# Clock_Distribution.net
KiCad netlist of a schematic drawn in Altium Designer
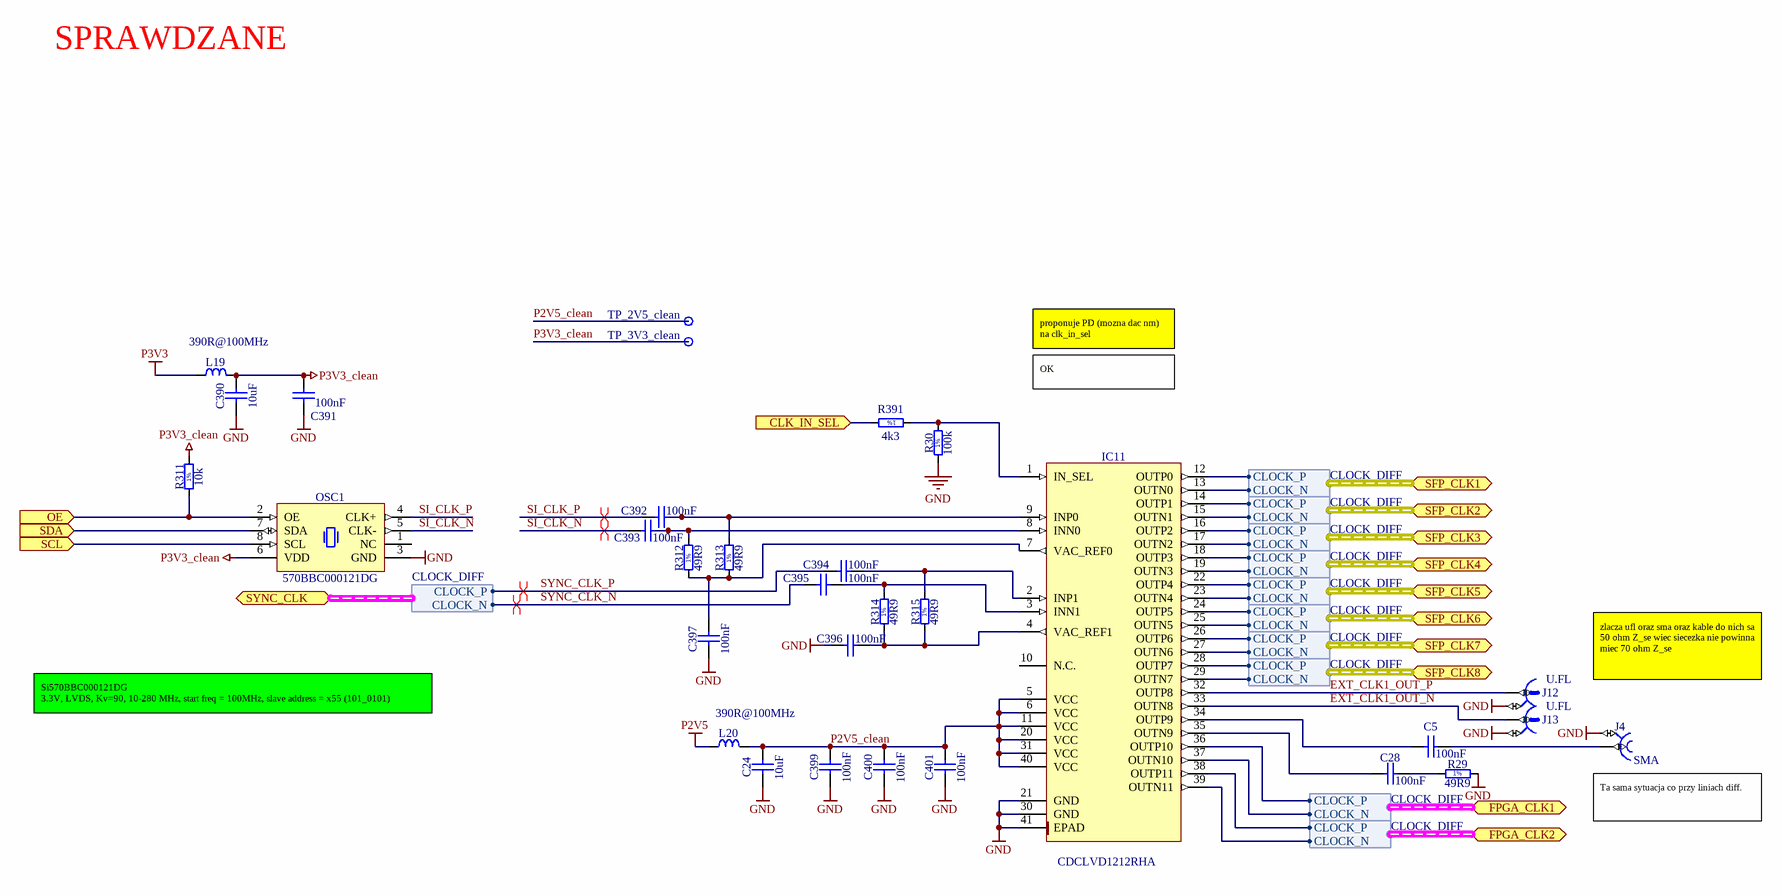
[diagram p0: Clock_Distribution.SchDoc]

(export (version "E")
  (design (tool "Eeschema 10.0.6"))
  (components
    (comp (ref "C5")
      (value "100nF")
      (footprint "CAPC1005X55N")
      (description "Non-polarised capacitor")
      (fields
        (field (name "PART NUMBER") "CC0402_100NF_16V_10%_X7R")
        (field (name "VOLTAGE") "16V")
        (field (name "AUTHOR") "CERN DEM JLC")
      )
      (libsource (lib "Capacitors") (part "Capacitor - non polarized"))
    )
    (comp (ref "C24")
      (value "10uF")
      (footprint "CAPC2012X135N")
      (description "Non-polarised capacitor")
      (fields
        (field (name "PART NUMBER") "CC0805_10UF_10V_10%_X7R")
        (field (name "VOLTAGE") "10V")
        (field (name "AUTHOR") "CERN DEM JLC")
      )
      (libsource (lib "Capacitors") (part "Capacitor - non polarized"))
    )
    (comp (ref "C28")
      (value "100nF")
      (footprint "CAPC1005X55N")
      (description "Non-polarised capacitor")
      (fields
        (field (name "PART NUMBER") "CC0402_100NF_16V_10%_X7R")
        (field (name "VOLTAGE") "16V")
        (field (name "AUTHOR") "CERN DEM JLC")
      )
      (libsource (lib "Capacitors") (part "Capacitor - non polarized"))
    )
    (comp (ref "C390")
      (value "10uF")
      (footprint "CAPC2012X135N")
      (description "Non-polarised capacitor")
      (fields
        (field (name "PART NUMBER") "CC0805_10UF_10V_10%_X7R")
        (field (name "VOLTAGE") "10V")
        (field (name "AUTHOR") "CERN DEM JLC")
      )
      (libsource (lib "Capacitors") (part "Capacitor - non polarized"))
    )
    (comp (ref "C391")
      (value "100nF")
      (footprint "CAPC0603X33N")
      (description "Non-polarised capacitor")
      (fields
        (field (name "PART NUMBER") "CC0201_100NF_6.3V_10%_X5R")
        (field (name "VOLTAGE") "6.3V")
        (field (name "AUTHOR") "CERN DEM JLC")
      )
      (libsource (lib "Capacitors") (part "Capacitor - non polarized"))
    )
    (comp (ref "C392")
      (value "100nF")
      (footprint "CAPC0603X33N")
      (description "Non-polarised capacitor")
      (fields
        (field (name "PART NUMBER") "CC0201_100NF_6.3V_10%_X5R")
        (field (name "VOLTAGE") "6.3V")
        (field (name "AUTHOR") "CERN DEM JLC")
      )
      (libsource (lib "Capacitors") (part "Capacitor - non polarized"))
    )
    (comp (ref "C393")
      (value "100nF")
      (footprint "CAPC0603X33N")
      (description "Non-polarised capacitor")
      (fields
        (field (name "PART NUMBER") "CC0201_100NF_6.3V_10%_X5R")
        (field (name "VOLTAGE") "6.3V")
        (field (name "AUTHOR") "CERN DEM JLC")
      )
      (libsource (lib "Capacitors") (part "Capacitor - non polarized"))
    )
    (comp (ref "C394")
      (value "100nF")
      (footprint "CAPC0603X33N")
      (description "Non-polarised capacitor")
      (fields
        (field (name "PART NUMBER") "CC0201_100NF_6.3V_10%_X5R")
        (field (name "VOLTAGE") "6.3V")
        (field (name "AUTHOR") "CERN DEM JLC")
      )
      (libsource (lib "Capacitors") (part "Capacitor - non polarized"))
    )
    (comp (ref "C395")
      (value "100nF")
      (footprint "CAPC0603X33N")
      (description "Non-polarised capacitor")
      (fields
        (field (name "PART NUMBER") "CC0201_100NF_6.3V_10%_X5R")
        (field (name "VOLTAGE") "6.3V")
        (field (name "AUTHOR") "CERN DEM JLC")
      )
      (libsource (lib "Capacitors") (part "Capacitor - non polarized"))
    )
    (comp (ref "C396")
      (value "100nF")
      (footprint "CAPC0603X33N")
      (description "Non-polarised capacitor")
      (fields
        (field (name "PART NUMBER") "CC0201_100NF_6.3V_10%_X5R")
        (field (name "VOLTAGE") "6.3V")
        (field (name "AUTHOR") "CERN DEM JLC")
      )
      (libsource (lib "Capacitors") (part "Capacitor - non polarized"))
    )
    (comp (ref "C397")
      (value "100nF")
      (footprint "CAPC0603X33N")
      (description "Non-polarised capacitor")
      (fields
        (field (name "PART NUMBER") "CC0201_100NF_6.3V_10%_X5R")
        (field (name "VOLTAGE") "6.3V")
        (field (name "AUTHOR") "CERN DEM JLC")
      )
      (libsource (lib "Capacitors") (part "Capacitor - non polarized"))
    )
    (comp (ref "C399")
      (value "100nF")
      (footprint "CAPC0603X33N")
      (description "Non-polarised capacitor")
      (fields
        (field (name "PART NUMBER") "CC0201_100NF_6.3V_10%_X5R")
        (field (name "VOLTAGE") "6.3V")
        (field (name "AUTHOR") "CERN DEM JLC")
      )
      (libsource (lib "Capacitors") (part "Capacitor - non polarized"))
    )
    (comp (ref "C400")
      (value "100nF")
      (footprint "CAPC0603X33N")
      (description "Non-polarised capacitor")
      (fields
        (field (name "PART NUMBER") "CC0201_100NF_6.3V_10%_X5R")
        (field (name "VOLTAGE") "6.3V")
        (field (name "AUTHOR") "CERN DEM JLC")
      )
      (libsource (lib "Capacitors") (part "Capacitor - non polarized"))
    )
    (comp (ref "C401")
      (value "100nF")
      (footprint "CAPC0603X33N")
      (description "Non-polarised capacitor")
      (fields
        (field (name "PART NUMBER") "CC0201_100NF_6.3V_10%_X5R")
        (field (name "VOLTAGE") "6.3V")
        (field (name "AUTHOR") "CERN DEM JLC")
      )
      (libsource (lib "Capacitors") (part "Capacitor - non polarized"))
    )
    (comp (ref "IC11")
      (value "CDCLVD1212RHA")
      (footprint "QFN50P600X600X80-41N-S425")
      (description "2:16 Low Additive Jitter LVDS Buffer")
      (fields (field (name "MANUFACTURER") "TEXAS INSTRUMENTS") (field (name "AUTHOR") "LNLS DIG LOS"))
      (libsource (lib "ICs And Semiconductors") (part "CDCLVD1212"))
    )
    (comp (ref "J4")
      (value "SMA")
      (footprint "HUBER-SUHNER_85_SMA-50-0-101/111_NE")
      (fields
        (field (name "PART NUMBER") "HUBER-SUHNER_85_SMA-50-0-101/111_NE")
        (field (name "MANUFACTURER") "HUBER+SUHNER")
        (field (name "MANUFACTURER PART NUMBER") "85_SMA-50-0-101/111_NE")
        (field (name "AUTHOR") "CERN DEM JLC")
      )
      (libsource (lib "Connectors") (part "Coax_1Female_1Shield"))
    )
    (comp (ref "J12")
      (value "U.FL")
      (footprint "HIROSE_U.FL-R-SMT-1(10)")
      (fields
        (field (name "PART NUMBER") "HIROSE_U.FL-R-SMT-1(10)")
        (field (name "MANUFACTURER") "HIROSE (HRS)")
        (field (name "MANUFACTURER PART NUMBER") "U.FL-R-SMT-1(10)")
        (field (name "AUTHOR") "CERN DEM JLC")
      )
      (libsource (lib "Connectors") (part "Coax_1Male_1Shield"))
    )
    (comp (ref "J13")
      (value "U.FL")
      (footprint "HIROSE_U.FL-R-SMT-1(10)")
      (fields
        (field (name "PART NUMBER") "HIROSE_U.FL-R-SMT-1(10)")
        (field (name "MANUFACTURER") "HIROSE (HRS)")
        (field (name "MANUFACTURER PART NUMBER") "U.FL-R-SMT-1(10)")
        (field (name "AUTHOR") "CERN DEM JLC")
      )
      (libsource (lib "Connectors") (part "Coax_1Male_1Shield"))
    )
    (comp (ref "L19")
      (value "390R@100MHz")
      (footprint "INDC1608X95N")
      (description "Inductor")
      (fields
        (field (name "PART NUMBER") "IND0603_TDK_MPZ1608R391A")
        (field (name "POWER") "1.2A")
        (field (name "AUTHOR") "CERN DEM JLC")
      )
      (libsource (lib "Inductors & Transformers") (part "Inductor"))
    )
    (comp (ref "L20")
      (value "390R@100MHz")
      (footprint "INDC1608X95N")
      (description "Inductor")
      (fields
        (field (name "PART NUMBER") "IND0603_TDK_MPZ1608R391A")
        (field (name "POWER") "1.2A")
        (field (name "AUTHOR") "CERN DEM JLC")
      )
      (libsource (lib "Inductors & Transformers") (part "Inductor"))
    )
    (comp (ref "OSC1")
      (value "570BBC000121DG")
      (footprint "OSC_SILICON-LAB_SI570")
      (description "Any-Rate I2C Programmable XO Oscillator Si570 Serie")
      (fields
        (field (name "PART NUMBER") "OSC_10-280MHZ_SILICON-LAB_Si570BBC000121DG")
        (field (name "MANUFACTURER") "SILICON LABS")
        (field (name "AUTHOR") "CERN DEM JLC")
      )
      (libsource (lib "ICs And Semiconductors") (part "Oscillator SILICON-LAB_Si570"))
    )
    (comp (ref "R29")
      (value "49R9")
      (footprint "RESC1005X40N")
      (description "Resistor - 1%")
      (fields
        (field (name "PART NUMBER") "R0402_49R9_1%_0.0625W_100PPM")
        (field (name "POWER") "0.0625W")
        (field (name "AUTHOR") "CERN DEM JLC")
      )
      (libsource (lib "Resistors") (part "Resistor - 1%"))
    )
    (comp (ref "R30")
      (value "100k")
      (footprint "RESC1608X55N")
      (description "Resistor - 1%")
      (fields
        (field (name "PART NUMBER") "R0603_100K_1%_0.1W_100PPM")
        (field (name "POWER") "0.1W")
        (field (name "AUTHOR") "CERN DEM JLC")
      )
      (libsource (lib "Resistors") (part "Resistor - 1%"))
    )
    (comp (ref "R311")
      (value "10k")
      (footprint "RESC1005X40N")
      (description "Resistor - 1%")
      (fields
        (field (name "PART NUMBER") "R0402_10K_1%_0.0625W_100PPM")
        (field (name "POWER") "0.0625W")
        (field (name "AUTHOR") "CERN DEM JLC")
      )
      (libsource (lib "Resistors") (part "Resistor - 1%"))
    )
    (comp (ref "R312")
      (value "49R9")
      (footprint "RESC1005X40N")
      (description "Resistor - 1%")
      (fields
        (field (name "PART NUMBER") "R0402_49R9_1%_0.0625W_100PPM")
        (field (name "POWER") "0.0625W")
        (field (name "AUTHOR") "CERN DEM JLC")
      )
      (libsource (lib "Resistors") (part "Resistor - 1%"))
    )
    (comp (ref "R313")
      (value "49R9")
      (footprint "RESC1005X40N")
      (description "Resistor - 1%")
      (fields
        (field (name "PART NUMBER") "R0402_49R9_1%_0.0625W_100PPM")
        (field (name "POWER") "0.0625W")
        (field (name "AUTHOR") "CERN DEM JLC")
      )
      (libsource (lib "Resistors") (part "Resistor - 1%"))
    )
    (comp (ref "R314")
      (value "49R9")
      (footprint "RESC1005X40N")
      (description "Resistor - 1%")
      (fields
        (field (name "PART NUMBER") "R0402_49R9_1%_0.0625W_100PPM")
        (field (name "POWER") "0.0625W")
        (field (name "AUTHOR") "CERN DEM JLC")
      )
      (libsource (lib "Resistors") (part "Resistor - 1%"))
    )
    (comp (ref "R315")
      (value "49R9")
      (footprint "RESC1005X40N")
      (description "Resistor - 1%")
      (fields
        (field (name "PART NUMBER") "R0402_49R9_1%_0.0625W_100PPM")
        (field (name "POWER") "0.0625W")
        (field (name "AUTHOR") "CERN DEM JLC")
      )
      (libsource (lib "Resistors") (part "Resistor - 1%"))
    )
    (comp (ref "R391")
      (value "4k3")
      (footprint "RESC1608X55N")
      (description "Resistor - 1%")
      (fields
        (field (name "PART NUMBER") "R0603_4K3_1%_0.1W_100PPM")
        (field (name "POWER") "0.1W")
        (field (name "AUTHOR") "CERN DEM JLC")
      )
      (libsource (lib "Resistors") (part "Resistor - 1%"))
    )
    (comp (ref "TP_2V5_clean")
      (value "Test Point")
      (footprint "TPS127")
      (fields (field (name "PART NUMBER") "SMD_PAD_1.27X1.27MM") (field (name "AUTHOR") "CERN DEM JLC"))
      (libsource (lib "Eletro-mechanical") (part "Test Point"))
    )
    (comp (ref "TP_3V3_clean")
      (value "Test Point")
      (footprint "TPS127")
      (fields (field (name "PART NUMBER") "SMD_PAD_1.27X1.27MM") (field (name "AUTHOR") "CERN DEM JLC"))
      (libsource (lib "Eletro-mechanical") (part "Test Point"))
    )
  )
  (nets
    (net (code "3") (name "/CLK_IN_SEL") (class "Default")
      (node (ref "R391") (pin "2") (pinfunction "2_2") (pintype "passive"))
    )
    (net (code "4") (name "/EXT_CLK1_OUT_N") (class "Default")
      (node (ref "IC11") (pin "33") (pinfunction "OUTN8_33") (pintype "output"))
      (node (ref "J13") (pin "1") (pinfunction "1_1") (pintype "bidirectional"))
    )
    (net (code "5") (name "/EXT_CLK1_OUT_P") (class "Default")
      (node (ref "IC11") (pin "32") (pinfunction "OUTP8_32") (pintype "output"))
      (node (ref "J12") (pin "1") (pinfunction "1_1") (pintype "bidirectional"))
    )
    (net (code "6") (name "/OE") (class "Default")
      (node (ref "OSC1") (pin "2") (pinfunction "OE_2") (pintype "input"))
      (node (ref "R311") (pin "1") (pinfunction "1_1") (pintype "passive"))
    )
    (net (code "7") (name "/P2V5_clean") (class "Default")
      (node (ref "C24") (pin "2") (pinfunction "2_2") (pintype "passive"))
      (node (ref "C399") (pin "2") (pinfunction "2_2") (pintype "passive"))
      (node (ref "C400") (pin "2") (pinfunction "2_2") (pintype "passive"))
      (node (ref "C401") (pin "2") (pinfunction "2_2") (pintype "passive"))
      (node (ref "IC11") (pin "11") (pinfunction "VCC_11") (pintype "power_in"))
      (node (ref "IC11") (pin "20") (pinfunction "VCC_20") (pintype "power_in"))
      (node (ref "IC11") (pin "31") (pinfunction "VCC_31") (pintype "power_in"))
      (node (ref "IC11") (pin "40") (pinfunction "VCC_40") (pintype "power_in"))
      (node (ref "IC11") (pin "5") (pinfunction "VCC_5") (pintype "power_in"))
      (node (ref "IC11") (pin "6") (pinfunction "VCC_6") (pintype "power_in"))
      (node (ref "L20") (pin "2") (pinfunction "2_2") (pintype "passive"))
      (node (ref "TP_2V5_clean") (pin "1") (pinfunction "1_1") (pintype "bidirectional"))
    )
    (net (code "8") (name "/SCL") (class "Default")
      (node (ref "OSC1") (pin "8") (pinfunction "SCL_8") (pintype "input"))
    )
    (net (code "9") (name "/SDA") (class "Default")
      (node (ref "OSC1") (pin "7") (pinfunction "SDA_7") (pintype "bidirectional"))
    )
    (net (code "11") (name "/SI_CLK_N") (class "Default")
      (node (ref "C393") (pin "2") (pinfunction "2_2") (pintype "passive"))
      (node (ref "OSC1") (pin "5") (pinfunction "CLK-_5") (pintype "output"))
    )
    (net (code "12") (name "/SI_CLK_P") (class "Default")
      (node (ref "C392") (pin "2") (pinfunction "2_2") (pintype "passive"))
      (node (ref "OSC1") (pin "4") (pinfunction "CLK+_4") (pintype "output"))
    )
    (net (code "13") (name "/SYNC_CLK_N") (class "Default")
      (node (ref "C395") (pin "2") (pinfunction "2_2") (pintype "passive"))
    )
    (net (code "14") (name "/SYNC_CLK_P") (class "Default")
      (node (ref "C394") (pin "2") (pinfunction "2_2") (pintype "passive"))
    )
    (net (code "16") (name "GND") (class "Default")
      (node (ref "C24") (pin "1") (pinfunction "1_1") (pintype "passive"))
      (node (ref "C390") (pin "1") (pinfunction "1_1") (pintype "passive"))
      (node (ref "C391") (pin "1") (pinfunction "1_1") (pintype "passive"))
      (node (ref "C396") (pin "1") (pinfunction "1_1") (pintype "passive"))
      (node (ref "C397") (pin "1") (pinfunction "1_1") (pintype "passive"))
      (node (ref "C399") (pin "1") (pinfunction "1_1") (pintype "passive"))
      (node (ref "C400") (pin "1") (pinfunction "1_1") (pintype "passive"))
      (node (ref "C401") (pin "1") (pinfunction "1_1") (pintype "passive"))
      (node (ref "IC11") (pin "21") (pinfunction "GND_21") (pintype "power_in"))
      (node (ref "IC11") (pin "30") (pinfunction "GND_30") (pintype "power_in"))
      (node (ref "IC11") (pin "41") (pinfunction "EPAD_41") (pintype "power_in"))
      (node (ref "J12") (pin "2") (pinfunction "2_2") (pintype "bidirectional"))
      (node (ref "J13") (pin "2") (pinfunction "2_2") (pintype "bidirectional"))
      (node (ref "J4") (pin "2") (pinfunction "2_2") (pintype "bidirectional"))
      (node (ref "OSC1") (pin "3") (pinfunction "GND_3") (pintype "power_in"))
      (node (ref "R29") (pin "2") (pinfunction "2_2") (pintype "passive"))
      (node (ref "R30") (pin "1") (pinfunction "1_1") (pintype "passive"))
    )
    (net (code "17") (name "Net-(C5-Pad2)") (class "Default")
      (node (ref "C5") (pin "2") (pinfunction "2_2") (pintype "passive"))
      (node (ref "J4") (pin "1") (pinfunction "1_1") (pintype "bidirectional"))
    )
    (net (code "18") (name "Net-(C28-Pad1)") (class "Default")
      (node (ref "C28") (pin "1") (pinfunction "1_1") (pintype "passive"))
      (node (ref "R29") (pin "1") (pinfunction "1_1") (pintype "passive"))
    )
    (net (code "19") (name "Net-(IC11-INN0)") (class "Default")
      (node (ref "C393") (pin "1") (pinfunction "1_1") (pintype "passive"))
      (node (ref "IC11") (pin "8") (pinfunction "INN0_8") (pintype "input"))
      (node (ref "R312") (pin "2") (pinfunction "2_2") (pintype "passive"))
    )
    (net (code "20") (name "Net-(IC11-INN1)") (class "Default")
      (node (ref "C395") (pin "1") (pinfunction "1_1") (pintype "passive"))
      (node (ref "IC11") (pin "3") (pinfunction "INN1_3") (pintype "input"))
      (node (ref "R314") (pin "2") (pinfunction "2_2") (pintype "passive"))
    )
    (net (code "21") (name "Net-(IC11-INP0)") (class "Default")
      (node (ref "C392") (pin "1") (pinfunction "1_1") (pintype "passive"))
      (node (ref "IC11") (pin "9") (pinfunction "INP0_9") (pintype "input"))
      (node (ref "R313") (pin "2") (pinfunction "2_2") (pintype "passive"))
    )
    (net (code "22") (name "Net-(IC11-INP1)") (class "Default")
      (node (ref "C394") (pin "1") (pinfunction "1_1") (pintype "passive"))
      (node (ref "IC11") (pin "2") (pinfunction "INP1_2") (pintype "input"))
      (node (ref "R315") (pin "2") (pinfunction "2_2") (pintype "passive"))
    )
    (net (code "23") (name "Net-(IC11-IN_SEL)") (class "Default")
      (node (ref "IC11") (pin "1") (pinfunction "IN_SEL_1") (pintype "input"))
      (node (ref "R30") (pin "2") (pinfunction "2_2") (pintype "passive"))
      (node (ref "R391") (pin "1") (pinfunction "1_1") (pintype "passive"))
    )
    (net (code "24") (name "Net-(IC11-OUTN9)") (class "Default")
      (node (ref "C28") (pin "2") (pinfunction "2_2") (pintype "passive"))
      (node (ref "IC11") (pin "35") (pinfunction "OUTN9_35") (pintype "output"))
    )
    (net (code "25") (name "Net-(IC11-OUTP9)") (class "Default")
      (node (ref "C5") (pin "1") (pinfunction "1_1") (pintype "passive"))
      (node (ref "IC11") (pin "34") (pinfunction "OUTP9_34") (pintype "output"))
    )
    (net (code "26") (name "Net-(IC11-VAC_REF0)") (class "Default")
      (node (ref "C397") (pin "2") (pinfunction "2_2") (pintype "passive"))
      (node (ref "IC11") (pin "7") (pinfunction "VAC_REF0_7") (pintype "output"))
      (node (ref "R312") (pin "1") (pinfunction "1_1") (pintype "passive"))
      (node (ref "R313") (pin "1") (pinfunction "1_1") (pintype "passive"))
    )
    (net (code "27") (name "Net-(IC11-VAC_REF1)") (class "Default")
      (node (ref "C396") (pin "2") (pinfunction "2_2") (pintype "passive"))
      (node (ref "IC11") (pin "4") (pinfunction "VAC_REF1_4") (pintype "output"))
      (node (ref "R314") (pin "1") (pinfunction "1_1") (pintype "passive"))
      (node (ref "R315") (pin "1") (pinfunction "1_1") (pintype "passive"))
    )
    (net (code "28") (name "P2V5") (class "Default")
      (node (ref "L20") (pin "1") (pinfunction "1_1") (pintype "passive"))
    )
    (net (code "29") (name "P3V3") (class "Default")
      (node (ref "L19") (pin "1") (pinfunction "1_1") (pintype "passive"))
    )
    (net (code "30") (name "P3V3_clean") (class "Default")
      (node (ref "C390") (pin "2") (pinfunction "2_2") (pintype "passive"))
      (node (ref "C391") (pin "2") (pinfunction "2_2") (pintype "passive"))
      (node (ref "L19") (pin "2") (pinfunction "2_2") (pintype "passive"))
      (node (ref "OSC1") (pin "6") (pinfunction "VDD_6") (pintype "power_in"))
      (node (ref "R311") (pin "2") (pinfunction "2_2") (pintype "passive"))
      (node (ref "TP_3V3_clean") (pin "1") (pinfunction "1_1") (pintype "bidirectional"))
    )
    (net (code "31") (name "unconnected-(IC11-N.C.-Pad10)") (class "Default")
      (node (ref "IC11") (pin "10") (pinfunction "N.C._10") (pintype "passive"))
    )
    (net (code "32") (name "unconnected-(IC11-OUTN0-Pad13)") (class "Default")
      (node (ref "IC11") (pin "13") (pinfunction "OUTN0_13") (pintype "output"))
    )
    (net (code "33") (name "unconnected-(IC11-OUTN1-Pad15)") (class "Default")
      (node (ref "IC11") (pin "15") (pinfunction "OUTN1_15") (pintype "output"))
    )
    (net (code "34") (name "unconnected-(IC11-OUTN2-Pad17)") (class "Default")
      (node (ref "IC11") (pin "17") (pinfunction "OUTN2_17") (pintype "output"))
    )
    (net (code "35") (name "unconnected-(IC11-OUTN3-Pad19)") (class "Default")
      (node (ref "IC11") (pin "19") (pinfunction "OUTN3_19") (pintype "output"))
    )
    (net (code "36") (name "unconnected-(IC11-OUTN4-Pad23)") (class "Default")
      (node (ref "IC11") (pin "23") (pinfunction "OUTN4_23") (pintype "output"))
    )
    (net (code "37") (name "unconnected-(IC11-OUTN5-Pad25)") (class "Default")
      (node (ref "IC11") (pin "25") (pinfunction "OUTN5_25") (pintype "output"))
    )
    (net (code "38") (name "unconnected-(IC11-OUTN6-Pad27)") (class "Default")
      (node (ref "IC11") (pin "27") (pinfunction "OUTN6_27") (pintype "output"))
    )
    (net (code "39") (name "unconnected-(IC11-OUTN7-Pad29)") (class "Default")
      (node (ref "IC11") (pin "29") (pinfunction "OUTN7_29") (pintype "output"))
    )
    (net (code "40") (name "unconnected-(IC11-OUTN10-Pad37)") (class "Default")
      (node (ref "IC11") (pin "37") (pinfunction "OUTN10_37") (pintype "output"))
    )
    (net (code "41") (name "unconnected-(IC11-OUTN11-Pad39)") (class "Default")
      (node (ref "IC11") (pin "39") (pinfunction "OUTN11_39") (pintype "output"))
    )
    (net (code "42") (name "unconnected-(IC11-OUTP0-Pad12)") (class "Default")
      (node (ref "IC11") (pin "12") (pinfunction "OUTP0_12") (pintype "output"))
    )
    (net (code "43") (name "unconnected-(IC11-OUTP1-Pad14)") (class "Default")
      (node (ref "IC11") (pin "14") (pinfunction "OUTP1_14") (pintype "output"))
    )
    (net (code "44") (name "unconnected-(IC11-OUTP2-Pad16)") (class "Default")
      (node (ref "IC11") (pin "16") (pinfunction "OUTP2_16") (pintype "output"))
    )
    (net (code "45") (name "unconnected-(IC11-OUTP3-Pad18)") (class "Default")
      (node (ref "IC11") (pin "18") (pinfunction "OUTP3_18") (pintype "output"))
    )
    (net (code "46") (name "unconnected-(IC11-OUTP4-Pad22)") (class "Default")
      (node (ref "IC11") (pin "22") (pinfunction "OUTP4_22") (pintype "output"))
    )
    (net (code "47") (name "unconnected-(IC11-OUTP5-Pad24)") (class "Default")
      (node (ref "IC11") (pin "24") (pinfunction "OUTP5_24") (pintype "output"))
    )
    (net (code "48") (name "unconnected-(IC11-OUTP6-Pad26)") (class "Default")
      (node (ref "IC11") (pin "26") (pinfunction "OUTP6_26") (pintype "output"))
    )
    (net (code "49") (name "unconnected-(IC11-OUTP7-Pad28)") (class "Default")
      (node (ref "IC11") (pin "28") (pinfunction "OUTP7_28") (pintype "output"))
    )
    (net (code "50") (name "unconnected-(IC11-OUTP10-Pad36)") (class "Default")
      (node (ref "IC11") (pin "36") (pinfunction "OUTP10_36") (pintype "output"))
    )
    (net (code "51") (name "unconnected-(IC11-OUTP11-Pad38)") (class "Default")
      (node (ref "IC11") (pin "38") (pinfunction "OUTP11_38") (pintype "output"))
    )
    (net (code "52") (name "unconnected-(OSC1-NC-Pad1)") (class "Default")
      (node (ref "OSC1") (pin "1") (pinfunction "NC_1") (pintype "passive"))
    )
  )
)
